# Real_Time_Clock.net
KiCad netlist of a schematic drawn in Altium Designer
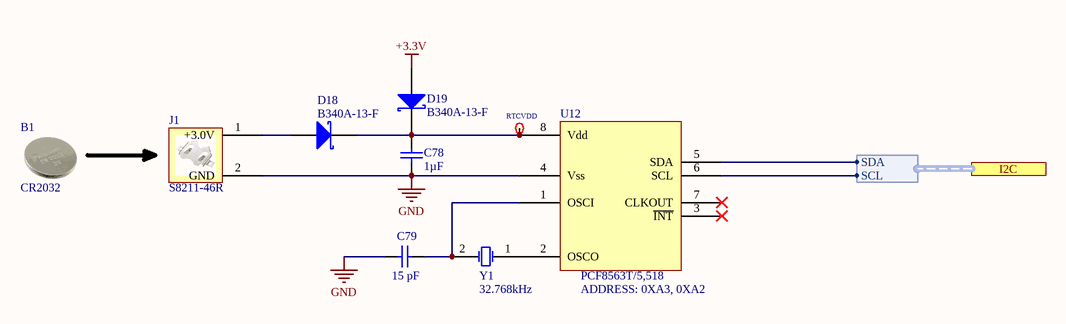
[diagram p0: Real Time Clock.SchDoc]

(export (version "E")
  (design (tool "Eeschema 10.0.6"))
  (components
    (comp (ref "B1")
      (value "CR2032")
      (fields (field (name "MANUFACTURER") "Panasonic - BSG"))
      (libsource (lib "LIFECHOICE+ SCHLIB") (part "CR2032"))
    )
    (comp (ref "C78")
      (value "50V")
      (footprint "0402C")
      (description "CAP .1UF 50V CERAMIC Y5V 0805")
      (fields
        (field (name "MANUFACTURER") "TDK")
        (field (name "MANUFACTURER PART NUMBER") "CGB2A1JB1C105K033BC")
        (field (name "CAPACITANCE") "1µF")
      )
      (libsource (lib "Miscellaneous Devices") (part "Cap"))
    )
    (comp (ref "C79")
      (value "50V")
      (footprint "0402C")
      (description "CAP .1UF 50V CERAMIC Y5V 0805")
      (fields
        (field (name "MANUFACTURER") "Johanson")
        (field (name "MANUFACTURER PART NUMBER") "500R07N150JV4T")
        (field (name "CAPACITANCE") "15 pF")
      )
      (libsource (lib "Miscellaneous Devices") (part "Cap"))
    )
    (comp (ref "D18")
      (value "BAT46ZFILM")
      (footprint "SMA")
      (description "Schottky Rectifier")
      (fields
        (field (name "MANUFACTURER") "Diodes Incorporated")
        (field (name "MANUFACTURER PART NUMBER") "B340A-13-F")
      )
      (libsource (lib "EEG_SCHLIB") (part "BAT46ZFILM"))
    )
    (comp (ref "D19")
      (value "BAT46ZFILM")
      (footprint "SMA")
      (description "Schottky Rectifier")
      (fields
        (field (name "MANUFACTURER") "Diodes Incorporated")
        (field (name "MANUFACTURER PART NUMBER") "B340A-13-F")
      )
      (libsource (lib "EEG_SCHLIB") (part "BAT46ZFILM"))
    )
    (comp (ref "J1")
      (value "S8211-46R")
      (footprint "CR2032 ASSEMBLY")
      (fields (field (name "MANUFACTURER") "Harwin Inc"))
      (libsource (lib "LIFECHOICE+ SCHLIB") (part "S8211-46R"))
    )
    (comp (ref "RTCVDD")
      (value "5001")
      (footprint "KEYSTONE TP")
      (fields (field (name "MANUFACTURER") "Keystone Electronics"))
      (libsource (lib "UTF SCHLIB") (part "5001"))
    )
    (comp (ref "U12")
      (value "PCF8563T/5,518")
      (footprint "SO-8")
      (fields (field (name "MANUFACTURER") "NXP Semiconductors") (field (name "ADDRESS") "0XA3, 0XA2"))
      (libsource (lib "LIFECHOICE+ SCHLIB") (part "PCF8563T/5,518"))
    )
    (comp (ref "Y1")
      (value "32.768kHz")
      (footprint "ABS10")
      (description "Crystal Oscillator")
      (fields
        (field (name "MANUFACTURER") "Abracon Corporation")
        (field (name "MANUFACTURER PART NUMBER") "ABS10-32.768KHZ-T")
      )
      (libsource (lib "Miscellaneous Devices") (part "XTAL"))
    )
  )
  (nets
    (net (code "2") (name "+3.3V") (class "Default")
      (node (ref "D19") (pin "1") (pinfunction "A_1") (pintype "passive"))
    )
    (net (code "3") (name "/SCL") (class "Default")
      (node (ref "U12") (pin "6") (pinfunction "SCL_6") (pintype "passive"))
    )
    (net (code "4") (name "/SDA") (class "Default")
      (node (ref "U12") (pin "5") (pinfunction "SDA_5") (pintype "passive"))
    )
    (net (code "6") (name "GND") (class "Default")
      (node (ref "C78") (pin "2") (pinfunction "2_2") (pintype "passive"))
      (node (ref "C79") (pin "1") (pinfunction "1_1") (pintype "passive"))
      (node (ref "J1") (pin "2") (pinfunction "GND_2") (pintype "passive"))
      (node (ref "U12") (pin "4") (pinfunction "Vss_4") (pintype "passive"))
    )
    (net (code "7") (name "Net-(D18-A)") (class "Default")
      (node (ref "D18") (pin "1") (pinfunction "A_1") (pintype "passive"))
      (node (ref "J1") (pin "1") (pinfunction "+3.0V_1") (pintype "passive"))
    )
    (net (code "8") (name "Net-(D18-K)") (class "Default")
      (node (ref "C78") (pin "1") (pinfunction "1_1") (pintype "passive"))
      (node (ref "D18") (pin "2") (pinfunction "K_2") (pintype "passive"))
      (node (ref "D19") (pin "2") (pinfunction "K_2") (pintype "passive"))
      (node (ref "RTCVDD") (pin "1") (pinfunction "1_1") (pintype "passive"))
      (node (ref "U12") (pin "8") (pinfunction "Vdd_8") (pintype "passive"))
    )
    (net (code "9") (name "Net-(U12-OSCI)") (class "Default")
      (node (ref "C79") (pin "2") (pinfunction "2_2") (pintype "passive"))
      (node (ref "U12") (pin "1") (pinfunction "OSCI_1") (pintype "passive"))
      (node (ref "Y1") (pin "2") (pinfunction "OSC2_2") (pintype "passive"))
    )
    (net (code "10") (name "Net-(U12-OSCO)") (class "Default")
      (node (ref "U12") (pin "2") (pinfunction "OSCO_2") (pintype "passive"))
      (node (ref "Y1") (pin "1") (pinfunction "OSC1_1") (pintype "passive"))
    )
    (net (code "11") (name "unconnected-(U12-CLKOUT-Pad7)") (class "Default")
      (node (ref "U12") (pin "7") (pinfunction "CLKOUT_7") (pintype "passive+no_connect"))
    )
    (net (code "12") (name "unconnected-(U12-~{INT}-Pad3)") (class "Default")
      (node (ref "U12") (pin "3") (pinfunction "~{INT}_3") (pintype "passive+no_connect"))
    )
  )
)
